# 2S_TP5100_ETA3000.net
KiCad netlist of a schematic drawn in EasyEDA Pro
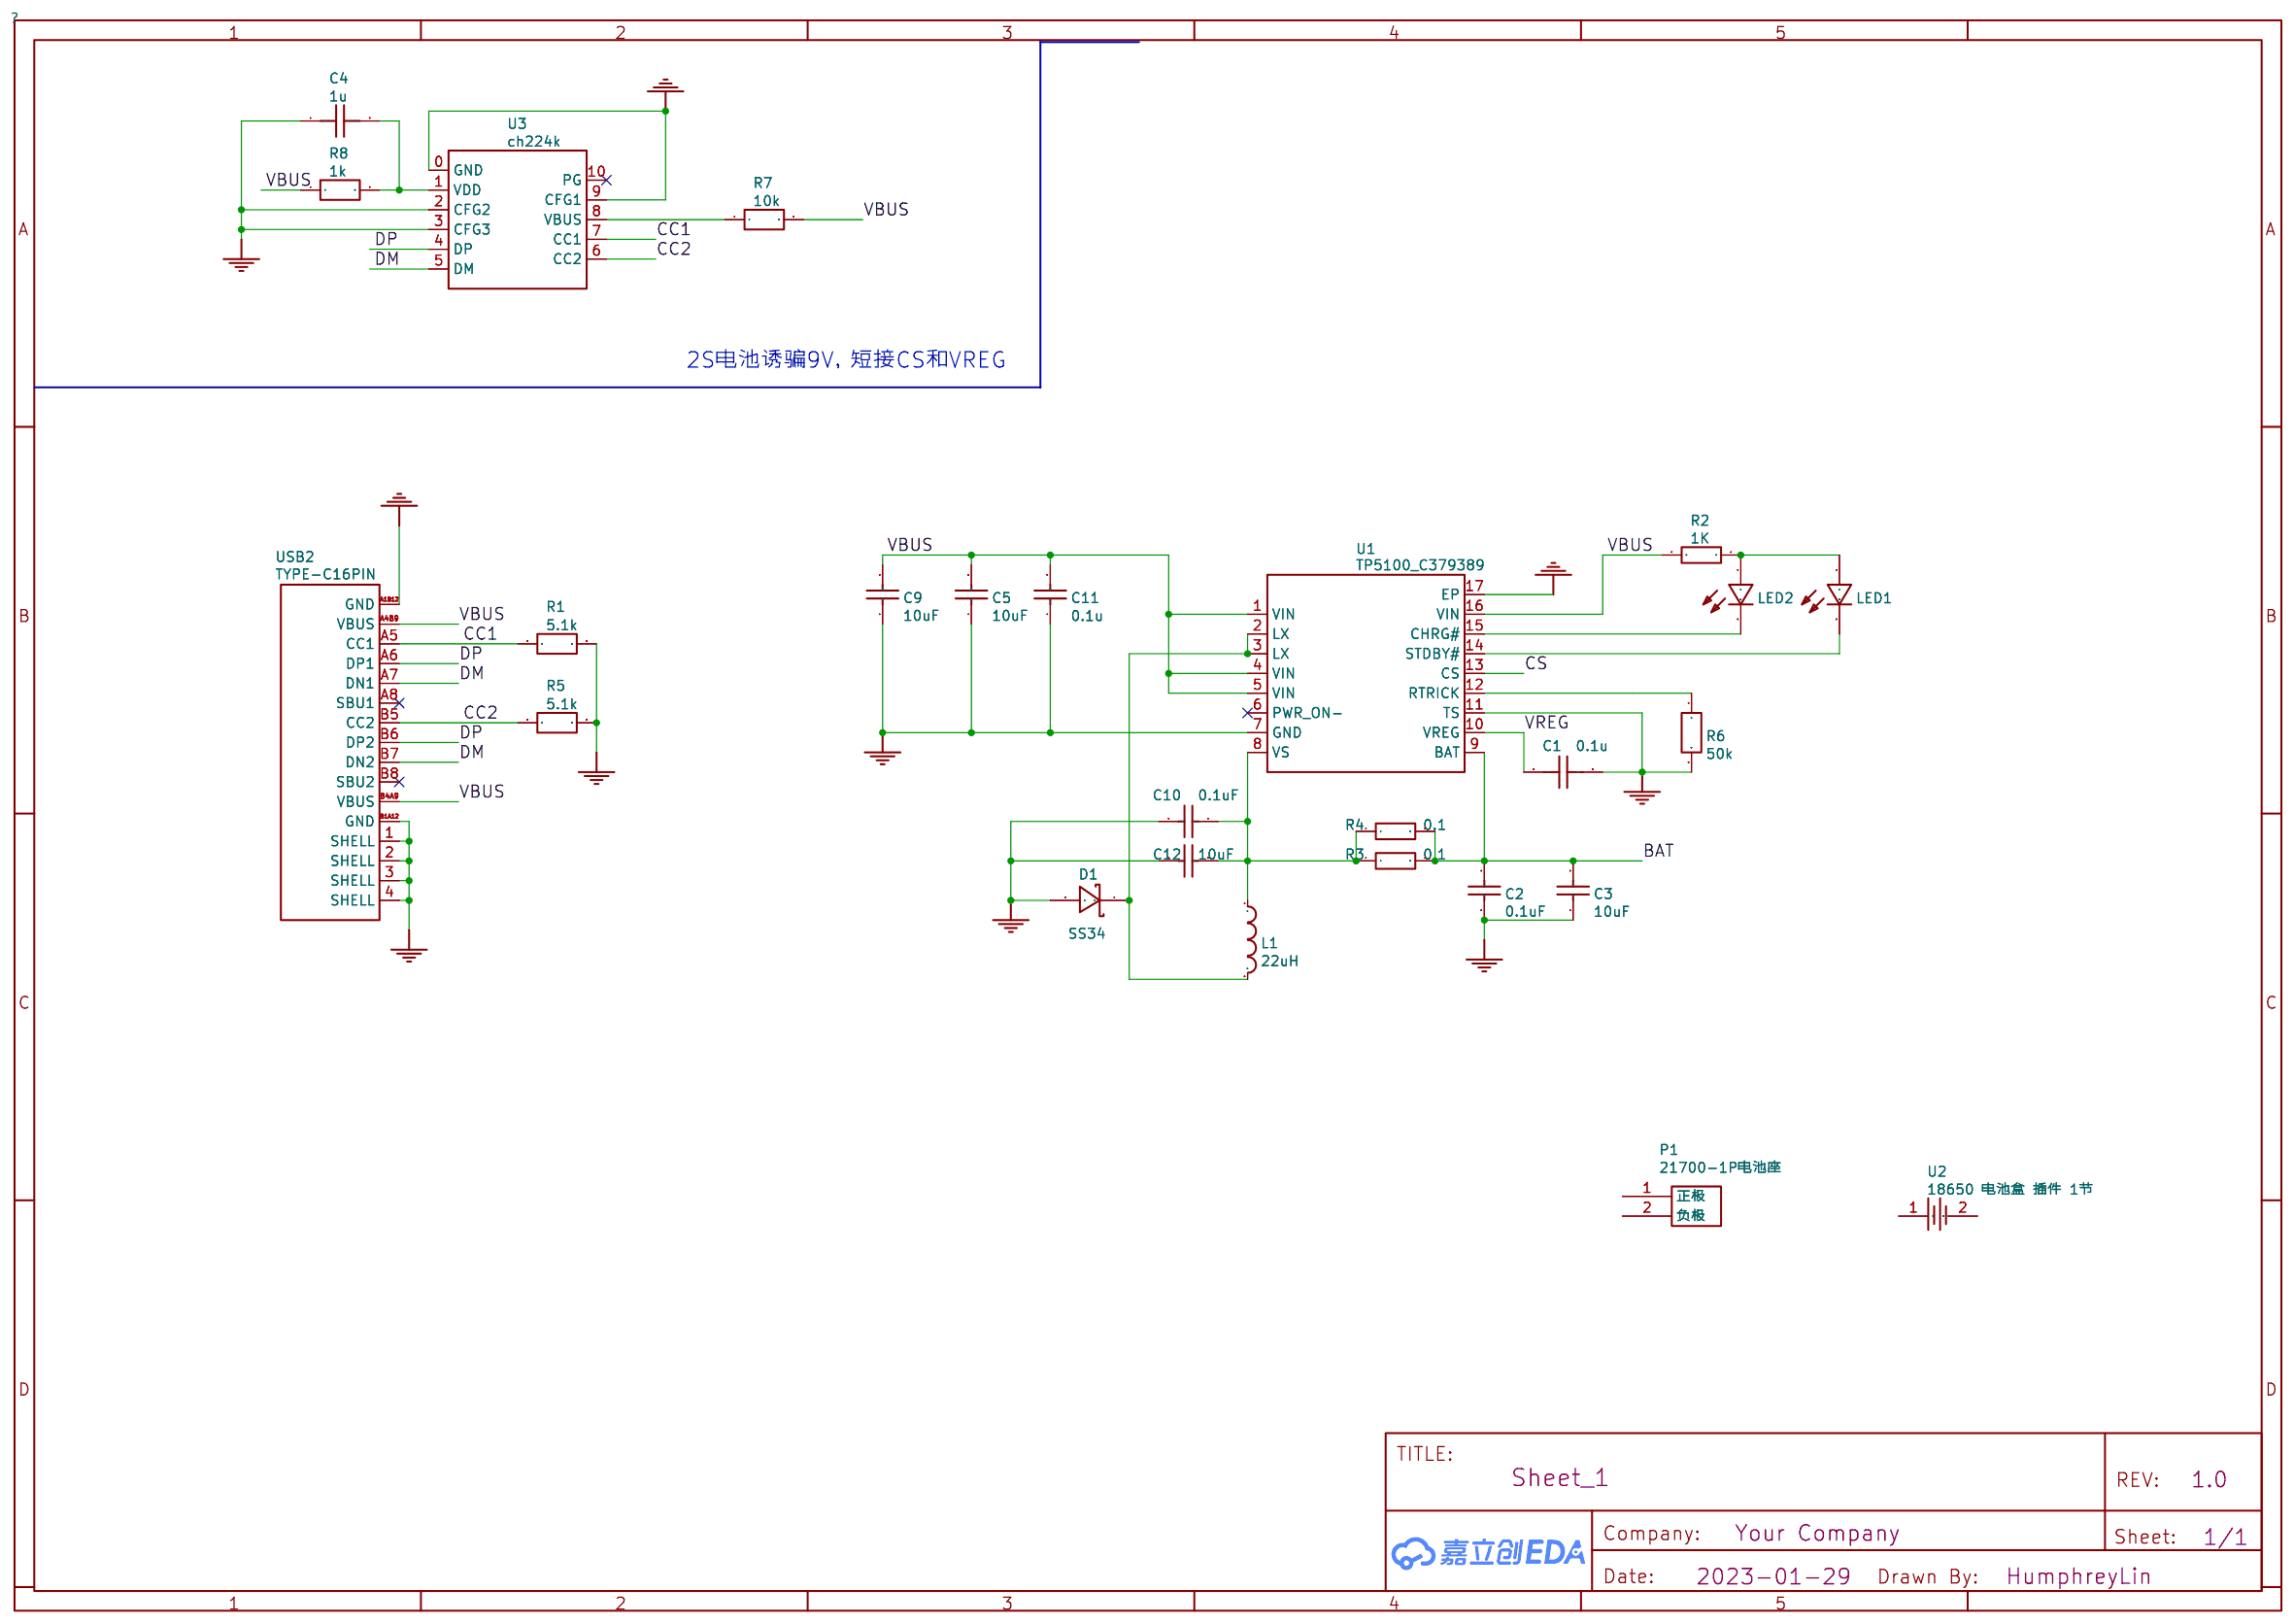
[diagram p0: schematic sheet]

(export (version "E")
  (design (tool "Eeschema 10.0.6"))
  (components
    (comp (ref "C1")
      (value "0.1u")
      (footprint "easyedapro:C0603")
      (fields (field (name "Contributor") "LCEDA_Lib"))
      (libsource (lib "easyedapro") (part "0.1u"))
    )
    (comp (ref "C2")
      (value "0.1uF")
      (footprint "easyedapro:C0603")
      (fields (field (name "Manufacturer Part") "CL31A106KAHNNNE") (field (name "Manufacturer") "SAMSUNG"))
      (libsource (lib "easyedapro") (part "0.1uF"))
    )
    (comp (ref "C3")
      (value "10uF")
      (footprint "easyedapro:C1206")
      (fields (field (name "Manufacturer Part") "CL31A106KAHNNNE") (field (name "Manufacturer") "SAMSUNG"))
      (libsource (lib "easyedapro") (part "10uF"))
    )
    (comp (ref "C4")
      (value "1u")
      (footprint "easyedapro:C0603")
      (fields (field (name "Contributor") "LCEDA_Lib"))
      (libsource (lib "easyedapro") (part "1u"))
    )
    (comp (ref "C5")
      (value "10uF")
      (footprint "easyedapro:C1206")
      (fields (field (name "Manufacturer Part") "CL31A106KAHNNNE") (field (name "Manufacturer") "SAMSUNG"))
      (libsource (lib "easyedapro") (part "10uF"))
    )
    (comp (ref "C9")
      (value "10uF")
      (footprint "easyedapro:C1206")
      (fields (field (name "Manufacturer Part") "CL31A106KAHNNNE") (field (name "Manufacturer") "SAMSUNG"))
      (libsource (lib "easyedapro") (part "10uF"))
    )
    (comp (ref "C10")
      (value "0.1uF")
      (footprint "easyedapro:C0603")
      (fields (field (name "Manufacturer Part") "CL31A106KAHNNNE") (field (name "Manufacturer") "SAMSUNG"))
      (libsource (lib "easyedapro") (part "0.1uF"))
    )
    (comp (ref "C11")
      (value "0.1u")
      (footprint "easyedapro:C0603")
      (fields (field (name "Manufacturer Part") "CL10B102KB8NNNC") (field (name "Manufacturer") "SAMSUNG"))
      (libsource (lib "") (part "0.1u_1"))
    )
    (comp (ref "C12")
      (value "10uF")
      (footprint "easyedapro:C1206")
      (fields (field (name "Manufacturer Part") "CL31A106KAHNNNE") (field (name "Manufacturer") "SAMSUNG"))
      (libsource (lib "easyedapro") (part "10uF"))
    )
    (comp (ref "D1")
      (value "SS34")
      (footprint "easyedapro:DO-214AC_L4.3-W2.7-LS5.3-RD")
      (fields (field (name "Manufacturer") "MDD"))
      (libsource (lib "easyedapro") (part "SS34"))
    )
    (comp (ref "L1")
      (value "22uH")
      (footprint "easyedapro:IND-SMD_L10.8-W10.0_SLO1040H")
      (fields
        (field (name "Manufacturer Part") "SLO1040H220MTT")
        (field (name "Manufacturer") "Sunltech")
        (field (name "Contributor") "LCSC")
      )
      (libsource (lib "easyedapro") (part "22uH"))
    )
    (comp (ref "LED1")
      (value "19-217/BHC-ZL1M2RY/3T")
      (footprint "easyedapro:LED0603-R-RD")
      (fields (field (name "Manufacturer") "EVERLIGHT"))
      (libsource (lib "easyedapro") (part "19-217/BHC-ZL1M2RY/3T"))
    )
    (comp (ref "LED2")
      (value "19-217/BHC-ZL1M2RY/3T")
      (footprint "easyedapro:LED0603-R-RD")
      (fields (field (name "Manufacturer") "EVERLIGHT"))
      (libsource (lib "easyedapro") (part "19-217/BHC-ZL1M2RY/3T"))
    )
    (comp (ref "P1")
      (value "21700-1P电池座")
      (fields (field (name "Contributor") "w764516453"))
      (libsource (lib "easyedapro") (part "21700-1P电池座"))
    )
    (comp (ref "R1")
      (value "5.1k")
      (footprint "easyedapro:R0603")
      (fields (field (name "Contributor") "LCEDA_Lib"))
      (libsource (lib "easyedapro") (part "5.1k"))
    )
    (comp (ref "R2")
      (value "1K")
      (footprint "easyedapro:R0603")
      (fields (field (name "Manufacturer Part") "0603WAF3302T5E") (field (name "Manufacturer") "UniOhm"))
      (libsource (lib "easyedapro") (part "1K"))
    )
    (comp (ref "R3")
      (value "0.1")
      (footprint "easyedapro:R1206")
      (fields (field (name "Manufacturer Part") "1206W4F100LT5E") (field (name "Manufacturer") "UniOhm"))
      (libsource (lib "easyedapro") (part "0.1"))
    )
    (comp (ref "R4")
      (value "0.1")
      (footprint "easyedapro:R1206")
      (fields (field (name "Manufacturer Part") "1206W4F100LT5E") (field (name "Manufacturer") "UniOhm"))
      (libsource (lib "easyedapro") (part "0.1"))
    )
    (comp (ref "R5")
      (value "5.1k")
      (footprint "easyedapro:R0603")
      (fields (field (name "Contributor") "LCEDA_Lib"))
      (libsource (lib "easyedapro") (part "5.1k"))
    )
    (comp (ref "R6")
      (value "50k")
      (footprint "easyedapro:R0603")
      (fields (field (name "Contributor") "LCEDA_Lib"))
      (libsource (lib "easyedapro") (part "50k"))
    )
    (comp (ref "R7")
      (value "10k")
      (footprint "easyedapro:R0603")
      (fields (field (name "Contributor") "LCEDA_Lib"))
      (libsource (lib "easyedapro") (part "10k"))
    )
    (comp (ref "R8")
      (value "1k")
      (footprint "easyedapro:R0805")
      (fields (field (name "Contributor") "LCEDA_Lib"))
      (libsource (lib "easyedapro") (part "1k"))
    )
    (comp (ref "U1")
      (value "TP5100_C379389")
      (footprint "easyedapro:TQFN-16_L4.0-W4.0-P0.65-BL-EP")
      (fields
        (field (name "Manufacturer Part") "TP5100")
        (field (name "Manufacturer") "Nanjing Extension Microelectronics")
        (field (name "Contributor") "LCSC")
      )
      (libsource (lib "easyedapro") (part "TP5100_C379389"))
    )
    (comp (ref "U2")
      (value "18650 电池盒 插件 1节")
      (fields (field (name "Contributor") "LCSC"))
      (libsource (lib "easyedapro") (part "18650 电池盒 插件 1节"))
    )
    (comp (ref "U3")
      (value "ch224k")
      (footprint "easyedapro:CH224K")
      (fields
        (field (name "Manufacturer Part") "CH224DS1")
        (field (name "Manufacturer") "WCH")
        (field (name "Contributor") "rxyuvty")
      )
      (libsource (lib "easyedapro") (part "ch224k"))
    )
    (comp (ref "USB2")
      (value "TYPE-C16PIN")
      (footprint "easyedapro:USB-C-SMD_TYPE-C16PIN")
      (fields (field (name "Manufacturer") "SHOU HAN") (field (name "Contributor") "LCSC"))
      (libsource (lib "easyedapro") (part "TYPE-C16PIN"))
    )
  )
  (nets
    (net (code "1") (name "/BAT") (class "Default")
      (node (ref "C2") (pin "2") (pinfunction "2_2") (pintype "input"))
      (node (ref "C3") (pin "2") (pinfunction "2_2") (pintype "input"))
      (node (ref "R3") (pin "2") (pinfunction "2_2") (pintype "input"))
      (node (ref "R4") (pin "2") (pinfunction "2_2") (pintype "input"))
      (node (ref "U1") (pin "9") (pinfunction "BAT_9") (pintype "unspecified"))
    )
    (net (code "2") (name "/CC1") (class "Default")
      (node (ref "R1") (pin "1") (pinfunction "1_1") (pintype "unspecified"))
      (node (ref "U3") (pin "7") (pinfunction "CC1_7") (pintype "unspecified"))
      (node (ref "USB2") (pin "A5") (pinfunction "CC1_A5") (pintype "unspecified"))
    )
    (net (code "3") (name "/CC2") (class "Default")
      (node (ref "R5") (pin "1") (pinfunction "1_1") (pintype "unspecified"))
      (node (ref "U3") (pin "6") (pinfunction "CC2_6") (pintype "unspecified"))
      (node (ref "USB2") (pin "B5") (pinfunction "CC2_B5") (pintype "unspecified"))
    )
    (net (code "4") (name "/CS") (class "Default")
      (node (ref "U1") (pin "13") (pinfunction "CS_13") (pintype "unspecified"))
    )
    (net (code "5") (name "/DM") (class "Default")
      (node (ref "U3") (pin "5") (pinfunction "DM_5") (pintype "unspecified"))
      (node (ref "USB2") (pin "A7") (pinfunction "DN1_A7") (pintype "unspecified"))
      (node (ref "USB2") (pin "B7") (pinfunction "DN2_B7") (pintype "unspecified"))
    )
    (net (code "6") (name "/DP") (class "Default")
      (node (ref "U3") (pin "4") (pinfunction "DP_4") (pintype "unspecified"))
      (node (ref "USB2") (pin "A6") (pinfunction "DP1_A6") (pintype "unspecified"))
      (node (ref "USB2") (pin "B6") (pinfunction "DP2_B6") (pintype "unspecified"))
    )
    (net (code "7") (name "/VBUS") (class "Default")
      (node (ref "C11") (pin "2") (pinfunction "2_2") (pintype "input"))
      (node (ref "C5") (pin "2") (pinfunction "2_2") (pintype "input"))
      (node (ref "C9") (pin "2") (pinfunction "2_2") (pintype "input"))
      (node (ref "R2") (pin "2") (pinfunction "2_2") (pintype "input"))
      (node (ref "R7") (pin "2") (pinfunction "2_2") (pintype "unspecified"))
      (node (ref "R8") (pin "1") (pinfunction "1_1") (pintype "unspecified"))
      (node (ref "U1") (pin "1") (pinfunction "VIN_1") (pintype "unspecified"))
      (node (ref "U1") (pin "16") (pinfunction "VIN_16") (pintype "unspecified"))
      (node (ref "U1") (pin "4") (pinfunction "VIN_4") (pintype "unspecified"))
      (node (ref "U1") (pin "5") (pinfunction "VIN_5") (pintype "unspecified"))
      (node (ref "USB2") (pin "A4B9") (pinfunction "VBUS_A4B9") (pintype "unspecified"))
      (node (ref "USB2") (pin "B4A9") (pinfunction "VBUS_B4A9") (pintype "unspecified"))
    )
    (net (code "8") (name "/VREG") (class "Default")
      (node (ref "C1") (pin "1") (pinfunction "1_1") (pintype "unspecified"))
      (node (ref "U1") (pin "10") (pinfunction "VREG_10") (pintype "unspecified"))
    )
    (net (code "9") (name "GND") (class "Default")
      (node (ref "C1") (pin "2") (pinfunction "2_2") (pintype "unspecified"))
      (node (ref "C10") (pin "2") (pinfunction "2_2") (pintype "input"))
      (node (ref "C11") (pin "1") (pinfunction "1_1") (pintype "input"))
      (node (ref "C12") (pin "1") (pinfunction "1_1") (pintype "input"))
      (node (ref "C2") (pin "1") (pinfunction "1_1") (pintype "input"))
      (node (ref "C3") (pin "1") (pinfunction "1_1") (pintype "input"))
      (node (ref "C4") (pin "1") (pinfunction "1_1") (pintype "unspecified"))
      (node (ref "C5") (pin "1") (pinfunction "1_1") (pintype "input"))
      (node (ref "C9") (pin "1") (pinfunction "1_1") (pintype "input"))
      (node (ref "D1") (pin "2") (pinfunction "A_2") (pintype "unspecified"))
      (node (ref "R1") (pin "2") (pinfunction "2_2") (pintype "unspecified"))
      (node (ref "R5") (pin "2") (pinfunction "2_2") (pintype "unspecified"))
      (node (ref "R6") (pin "2") (pinfunction "2_2") (pintype "unspecified"))
      (node (ref "U1") (pin "11") (pinfunction "TS_11") (pintype "unspecified"))
      (node (ref "U1") (pin "17") (pinfunction "EP_17") (pintype "unspecified"))
      (node (ref "U1") (pin "7") (pinfunction "GND_7") (pintype "unspecified"))
      (node (ref "U3") (pin "0") (pinfunction "GND_0") (pintype "unspecified"))
      (node (ref "U3") (pin "2") (pinfunction "CFG2_2") (pintype "unspecified"))
      (node (ref "U3") (pin "3") (pinfunction "CFG3_3") (pintype "unspecified"))
      (node (ref "U3") (pin "9") (pinfunction "CFG1_9") (pintype "unspecified"))
      (node (ref "USB2") (pin "1") (pinfunction "SHELL_1") (pintype "unspecified"))
      (node (ref "USB2") (pin "2") (pinfunction "SHELL_2") (pintype "unspecified"))
      (node (ref "USB2") (pin "3") (pinfunction "SHELL_3") (pintype "unspecified"))
      (node (ref "USB2") (pin "4") (pinfunction "SHELL_4") (pintype "unspecified"))
      (node (ref "USB2") (pin "A1B12") (pinfunction "GND_A1B12") (pintype "unspecified"))
      (node (ref "USB2") (pin "B1A12") (pinfunction "GND_B1A12") (pintype "unspecified"))
    )
    (net (code "10") (name "Net-(D1-K)") (class "Default")
      (node (ref "D1") (pin "1") (pinfunction "K_1") (pintype "unspecified"))
      (node (ref "L1") (pin "2") (pinfunction "2_2") (pintype "unspecified"))
      (node (ref "U1") (pin "2") (pinfunction "LX_2") (pintype "unspecified"))
      (node (ref "U1") (pin "3") (pinfunction "LX_3") (pintype "unspecified"))
    )
    (net (code "11") (name "Net-(LED1-A)") (class "Default")
      (node (ref "LED1") (pin "1") (pinfunction "A_1") (pintype "input"))
      (node (ref "LED2") (pin "1") (pinfunction "A_1") (pintype "input"))
      (node (ref "R2") (pin "1") (pinfunction "1_1") (pintype "input"))
    )
    (net (code "12") (name "Net-(LED1-C)") (class "Default")
      (node (ref "LED1") (pin "2") (pinfunction "C_2") (pintype "input"))
      (node (ref "U1") (pin "14") (pinfunction "STDBY#_14") (pintype "unspecified"))
    )
    (net (code "13") (name "Net-(LED2-C)") (class "Default")
      (node (ref "LED2") (pin "2") (pinfunction "C_2") (pintype "input"))
      (node (ref "U1") (pin "15") (pinfunction "CHRG#_15") (pintype "unspecified"))
    )
    (net (code "14") (name "Net-(U1-RTRICK)") (class "Default")
      (node (ref "R6") (pin "1") (pinfunction "1_1") (pintype "unspecified"))
      (node (ref "U1") (pin "12") (pinfunction "RTRICK_12") (pintype "unspecified"))
    )
    (net (code "15") (name "Net-(U1-VS)") (class "Default")
      (node (ref "C10") (pin "1") (pinfunction "1_1") (pintype "input"))
      (node (ref "C12") (pin "2") (pinfunction "2_2") (pintype "input"))
      (node (ref "L1") (pin "1") (pinfunction "1_1") (pintype "unspecified"))
      (node (ref "R3") (pin "1") (pinfunction "1_1") (pintype "input"))
      (node (ref "R4") (pin "1") (pinfunction "1_1") (pintype "input"))
      (node (ref "U1") (pin "8") (pinfunction "VS_8") (pintype "unspecified"))
    )
    (net (code "16") (name "Net-(U3-VBUS)") (class "Default")
      (node (ref "R7") (pin "1") (pinfunction "1_1") (pintype "unspecified"))
      (node (ref "U3") (pin "8") (pinfunction "VBUS_8") (pintype "unspecified"))
    )
    (net (code "17") (name "Net-(U3-VDD)") (class "Default")
      (node (ref "C4") (pin "2") (pinfunction "2_2") (pintype "unspecified"))
      (node (ref "R8") (pin "2") (pinfunction "2_2") (pintype "unspecified"))
      (node (ref "U3") (pin "1") (pinfunction "VDD_1") (pintype "unspecified"))
    )
    (net (code "18") (name "unconnected-(P1-正极-Pad1)") (class "Default")
      (node (ref "P1") (pin "1") (pinfunction "正极_1") (pintype "unspecified"))
    )
    (net (code "19") (name "unconnected-(P1-负极-Pad2)") (class "Default")
      (node (ref "P1") (pin "2") (pinfunction "负极_2") (pintype "unspecified"))
    )
    (net (code "20") (name "unconnected-(U1-PWR_ON--Pad6)") (class "Default")
      (node (ref "U1") (pin "6") (pinfunction "PWR_ON-_6") (pintype "unspecified+no_connect"))
    )
    (net (code "21") (name "unconnected-(U2-Pad1)") (class "Default")
      (node (ref "U2") (pin "1") (pinfunction "1_1") (pintype "input"))
    )
    (net (code "22") (name "unconnected-(U2-Pad2)") (class "Default")
      (node (ref "U2") (pin "2") (pinfunction "2_2") (pintype "input"))
    )
    (net (code "23") (name "unconnected-(U3-PG-Pad10)") (class "Default")
      (node (ref "U3") (pin "10") (pinfunction "PG_10") (pintype "unspecified+no_connect"))
    )
    (net (code "24") (name "unconnected-(USB2-SBU1-PadA8)") (class "Default")
      (node (ref "USB2") (pin "A8") (pinfunction "SBU1_A8") (pintype "unspecified+no_connect"))
    )
    (net (code "25") (name "unconnected-(USB2-SBU2-PadB8)") (class "Default")
      (node (ref "USB2") (pin "B8") (pinfunction "SBU2_B8") (pintype "unspecified+no_connect"))
    )
  )
)
